# RTC.net
KiCad netlist of a schematic drawn in Altium Designer
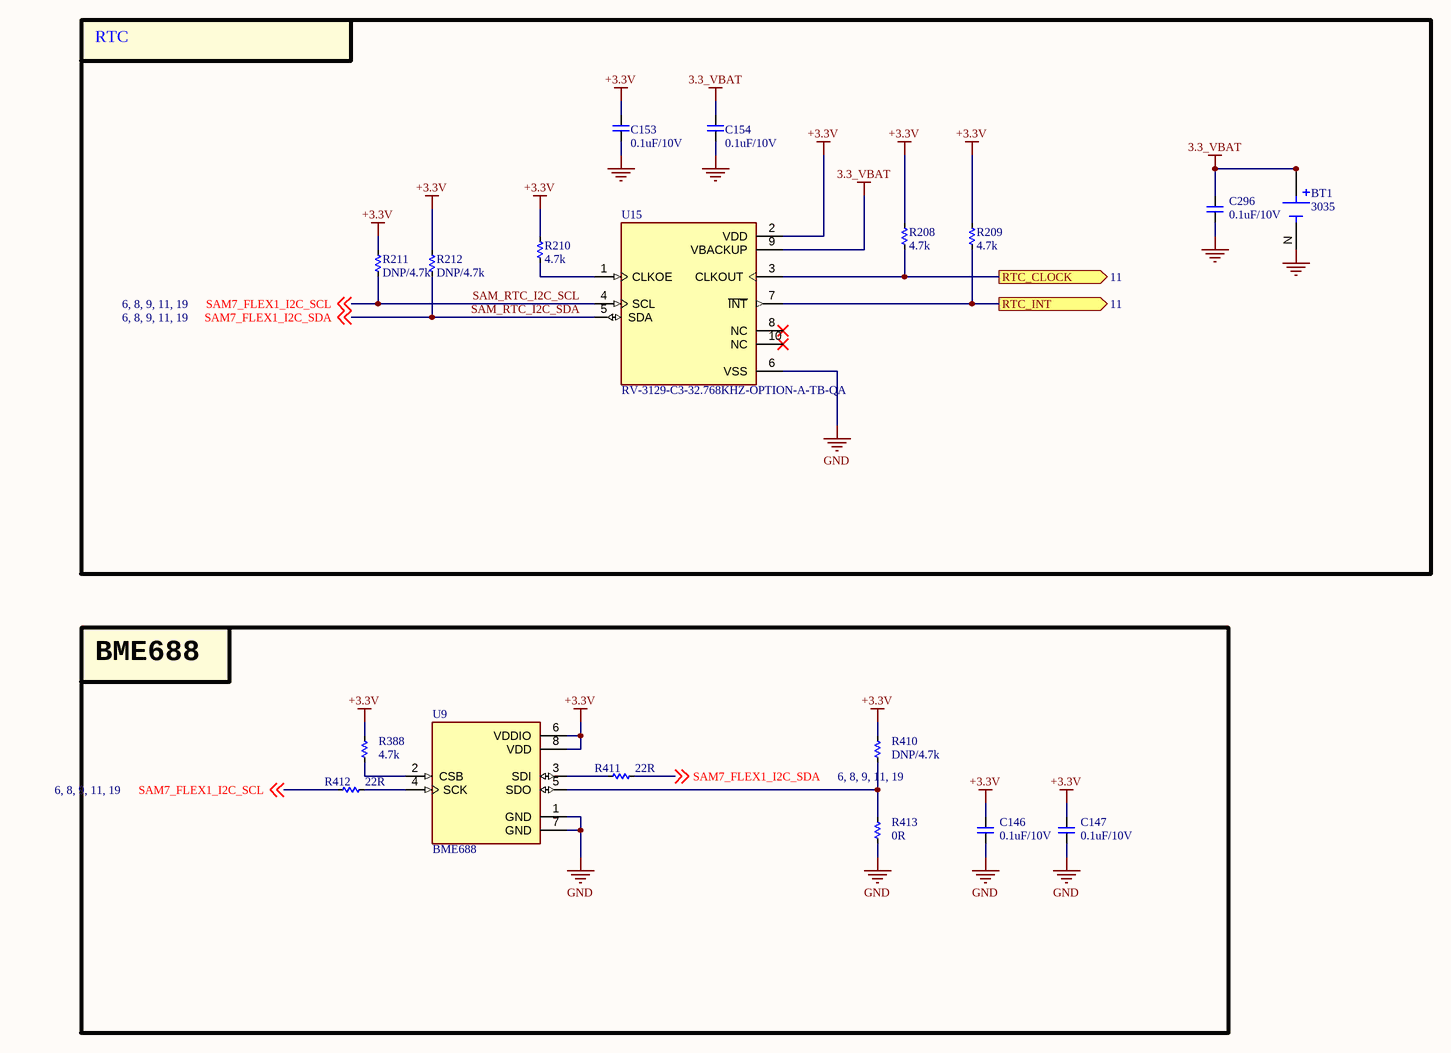
[diagram p0: RTC.SchDoc]

(export (version "E")
  (design (tool "Eeschema 10.0.6"))
  (components
    (comp (ref "BT1")
      (value "3035")
      (footprint "BAT_3035")
      (description "Battery Clip; THM; 20mm Cell; PhosBronze/Nickel ¦ Keystone Electronics 3035")
      (fields (field (name "MF") "Keystone Electronics"))
      (libsource (lib "LABLIB") (part "BT_HOLDER_3035"))
    )
    (comp (ref "C146")
      (value "0.1uF/10V")
      (footprint "CAP_C_1005X50_L")
      (description "CAP")
      (libsource (lib "LABLIB") (part "_CAP_C_2"))
    )
    (comp (ref "C147")
      (value "0.1uF/10V")
      (footprint "CAP_C_1005X50_L")
      (description "CAP")
      (libsource (lib "LABLIB") (part "_CAP_C_2"))
    )
    (comp (ref "C153")
      (value "0.1uF/10V")
      (footprint "CAP_C_1005X50_L")
      (description "CAP")
      (libsource (lib "LABLIB") (part "_CAP_C_2"))
    )
    (comp (ref "C154")
      (value "0.1uF/10V")
      (footprint "CAP_C_1005X50_L")
      (description "CAP")
      (libsource (lib "LABLIB") (part "_CAP_C_2"))
    )
    (comp (ref "C296")
      (value "0.1uF/10V")
      (footprint "CAP_C_1005X50_L")
      (description "CAP")
      (libsource (lib "LABLIB") (part "_CAP_C_2"))
    )
    (comp (ref "R208")
      (value "4.7k")
      (footprint "RES_C_1005x30_L")
      (description "RES")
      (libsource (lib "IFBschelib") (part "_RES_B_2"))
    )
    (comp (ref "R209")
      (value "4.7k")
      (footprint "RES_C_1005x30_L")
      (description "RES")
      (libsource (lib "IFBschelib") (part "_RES_B_2"))
    )
    (comp (ref "R210")
      (value "4.7k")
      (footprint "RES_C_1005x30_L")
      (description "RES")
      (libsource (lib "IFBschelib") (part "_RES_B_2"))
    )
    (comp (ref "R211")
      (value "DNP/4.7k")
      (footprint "RES_C_1005x30_L")
      (description "RES")
      (libsource (lib "IFBschelib") (part "_RES_B_2"))
    )
    (comp (ref "R212")
      (value "DNP/4.7k")
      (footprint "RES_C_1005x30_L")
      (description "RES")
      (libsource (lib "IFBschelib") (part "_RES_B_2"))
    )
    (comp (ref "R388")
      (value "4.7k")
      (footprint "RES_C_1005X40")
      (description "RES")
      (libsource (lib "LABLIB") (part "_RES_B_2"))
    )
    (comp (ref "R410")
      (value "DNP/4.7k")
      (footprint "RES_C_1005X40")
      (description "RES")
      (libsource (lib "LABLIB") (part "_RES_B_2"))
    )
    (comp (ref "R411")
      (value "22R")
      (footprint "RES_C_1005X40")
      (description "RES")
      (libsource (lib "LABLIB") (part "_RES_B_2"))
    )
    (comp (ref "R412")
      (value "22R")
      (footprint "RES_C_1005X40")
      (description "RES")
      (libsource (lib "LABLIB") (part "_RES_B_2"))
    )
    (comp (ref "R413")
      (value "0R")
      (footprint "RES_C_1005x30_L")
      (description "RES")
      (libsource (lib "LABLIB") (part "_RES_B_2"))
    )
    (comp (ref "U9")
      (value "BME688")
      (footprint "IC_BME688")
      (description "Gas sensor measuring relative humidity, barometric pressure, ambient temperature and gas (VOC)")
      (libsource (lib "LABLIB") (part "BME688"))
    )
    (comp (ref "U15")
      (value "RV-3129-C3-32.768KHZ-OPTION-A-TB-QA")
      (footprint "IC_RV-3129-C3-32.768KHZ-OPTION-A-TB-QA")
      (description "Real-Time Clock Module with I2C-Bus")
      (libsource (lib "IFBschelib") (part "RV-3129-C3-32.768KHZ-OPTION-A-TB-QA"))
    )
  )
  (nets
    (net (code "1") (name "+3.3V") (class "Default")
      (node (ref "C146") (pin "2") (pinfunction "2_2") (pintype "passive"))
      (node (ref "C147") (pin "2") (pinfunction "2_2") (pintype "passive"))
      (node (ref "C153") (pin "2") (pinfunction "2_2") (pintype "passive"))
      (node (ref "R208") (pin "1") (pinfunction "1_1") (pintype "passive"))
      (node (ref "R209") (pin "1") (pinfunction "1_1") (pintype "passive"))
      (node (ref "R210") (pin "1") (pinfunction "1_1") (pintype "passive"))
      (node (ref "R211") (pin "1") (pinfunction "1_1") (pintype "passive"))
      (node (ref "R212") (pin "1") (pinfunction "1_1") (pintype "passive"))
      (node (ref "R388") (pin "1") (pinfunction "1_1") (pintype "passive"))
      (node (ref "R410") (pin "1") (pinfunction "1_1") (pintype "passive"))
      (node (ref "U15") (pin "2") (pinfunction "VDD_2") (pintype "power_in"))
      (node (ref "U9") (pin "6") (pinfunction "VDDIO_6") (pintype "power_in"))
      (node (ref "U9") (pin "8") (pinfunction "VDD_8") (pintype "power_in"))
    )
    (net (code "2") (name "/RTC_CLOCK") (class "Default")
      (node (ref "R208") (pin "2") (pinfunction "2_2") (pintype "passive"))
      (node (ref "U15") (pin "3") (pinfunction "CLKOUT_3") (pintype "passive"))
    )
    (net (code "3") (name "/RTC_INT") (class "Default")
      (node (ref "R209") (pin "2") (pinfunction "2_2") (pintype "passive"))
      (node (ref "U15") (pin "7") (pinfunction "~{INT}_7") (pintype "output"))
    )
    (net (code "4") (name "3.3_VBAT") (class "Default")
      (node (ref "BT1") (pin "P1") (pinfunction "POS_P1") (pintype "passive"))
      (node (ref "BT1") (pin "P2") (pinfunction "POS_P2") (pintype "passive"))
      (node (ref "C154") (pin "2") (pinfunction "2_2") (pintype "passive"))
      (node (ref "C296") (pin "2") (pinfunction "2_2") (pintype "passive"))
      (node (ref "U15") (pin "9") (pinfunction "VBACKUP_9") (pintype "power_in"))
    )
    (net (code "5") (name "GND") (class "Default")
      (node (ref "BT1") (pin "N") (pinfunction "NEG_N") (pintype "passive"))
      (node (ref "C146") (pin "1") (pinfunction "1_1") (pintype "passive"))
      (node (ref "C147") (pin "1") (pinfunction "1_1") (pintype "passive"))
      (node (ref "C153") (pin "1") (pinfunction "1_1") (pintype "passive"))
      (node (ref "C154") (pin "1") (pinfunction "1_1") (pintype "passive"))
      (node (ref "C296") (pin "1") (pinfunction "1_1") (pintype "passive"))
      (node (ref "R413") (pin "2") (pinfunction "2_2") (pintype "passive"))
      (node (ref "U15") (pin "6") (pinfunction "VSS_6") (pintype "power_in"))
      (node (ref "U9") (pin "1") (pinfunction "GND_1") (pintype "power_in"))
      (node (ref "U9") (pin "7") (pinfunction "GND_7") (pintype "power_in"))
    )
    (net (code "6") (name "Net-(U9-CSB)") (class "Default")
      (node (ref "R388") (pin "2") (pinfunction "2_2") (pintype "passive"))
      (node (ref "U9") (pin "2") (pinfunction "CSB_2") (pintype "input"))
    )
    (net (code "7") (name "Net-(U9-SCK)") (class "Default")
      (node (ref "R412") (pin "2") (pinfunction "2_2") (pintype "passive"))
      (node (ref "U9") (pin "4") (pinfunction "SCK_4") (pintype "input"))
    )
    (net (code "8") (name "Net-(U9-SDI)") (class "Default")
      (node (ref "R411") (pin "1") (pinfunction "1_1") (pintype "passive"))
      (node (ref "U9") (pin "3") (pinfunction "SDI_3") (pintype "bidirectional"))
    )
    (net (code "9") (name "Net-(U9-SDO)") (class "Default")
      (node (ref "R410") (pin "2") (pinfunction "2_2") (pintype "passive"))
      (node (ref "R413") (pin "1") (pinfunction "1_1") (pintype "passive"))
      (node (ref "U9") (pin "5") (pinfunction "SDO_5") (pintype "bidirectional"))
    )
    (net (code "10") (name "Net-(U15-CLKOE)") (class "Default")
      (node (ref "R210") (pin "2") (pinfunction "2_2") (pintype "passive"))
      (node (ref "U15") (pin "1") (pinfunction "CLKOE_1") (pintype "input"))
    )
    (net (code "11") (name "SAM7_FLEX1_I2C_SCL") (class "Default")
      (node (ref "R211") (pin "2") (pinfunction "2_2") (pintype "passive"))
      (node (ref "R412") (pin "1") (pinfunction "1_1") (pintype "passive"))
      (node (ref "U15") (pin "4") (pinfunction "SCL_4") (pintype "input"))
    )
    (net (code "12") (name "SAM7_FLEX1_I2C_SDA") (class "Default")
      (node (ref "R212") (pin "2") (pinfunction "2_2") (pintype "passive"))
      (node (ref "R411") (pin "2") (pinfunction "2_2") (pintype "passive"))
      (node (ref "U15") (pin "5") (pinfunction "SDA_5") (pintype "bidirectional"))
    )
    (net (code "13") (name "unconnected-(U15-NC-Pad8)") (class "Default")
      (node (ref "U15") (pin "8") (pinfunction "NC_8") (pintype "passive+no_connect"))
    )
    (net (code "14") (name "unconnected-(U15-NC-Pad10)") (class "Default")
      (node (ref "U15") (pin "10") (pinfunction "NC_10") (pintype "passive+no_connect"))
    )
  )
)
